# RADC-RS485-S04-V00.net
KiCad netlist of a schematic drawn in Altium Designer
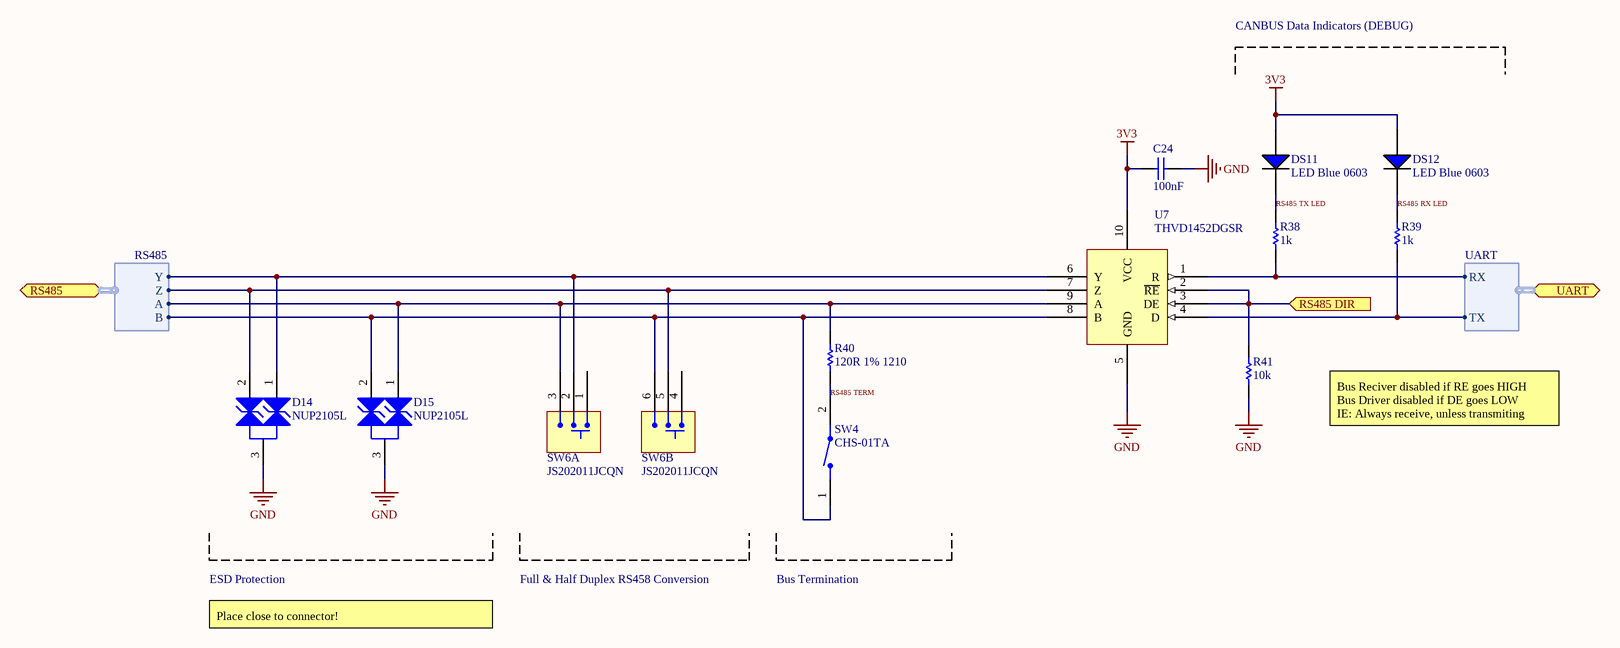
[diagram p0: RADC-RS485-S04-V00.SchDoc]

(export (version "E")
  (design (tool "Eeschema 10.0.6"))
  (components
    (comp (ref "C24")
      (value "100nF")
      (footprint "Cap_Ceramic_0603")
      (description "Capacitor, Ceramic, SMD, 100nF, 50V, 5%, X7R, 0603")
      (libsource (lib "StandardCapacitors") (part "100nF 50V 5% X7R 0603"))
    )
    (comp (ref "D14")
      (value "NUP2105L")
      (footprint "NUP2105L")
      (libsource (lib "QUTMS_CANLibrary") (part "NUP2105L"))
    )
    (comp (ref "D15")
      (value "NUP2105L")
      (footprint "NUP2105L")
      (libsource (lib "QUTMS_CANLibrary") (part "NUP2105L"))
    )
    (comp (ref "DS11")
      (value "LED Blue 0603")
      (footprint "LED BLUE 0603")
      (libsource (lib "QUTMS_LEDLibrary") (part "LED BLUE 0603"))
    )
    (comp (ref "DS12")
      (value "LED Blue 0603")
      (footprint "LED BLUE 0603")
      (libsource (lib "QUTMS_LEDLibrary") (part "LED BLUE 0603"))
    )
    (comp (ref "R38")
      (value "1k")
      (footprint "Res_ThinFilm_0603")
      (description "Resistor, SMD, 1k, 0.1W, 5%, 0603")
      (libsource (lib "StandardResistors") (part "1k 5% 0603"))
    )
    (comp (ref "R39")
      (value "1k")
      (footprint "Res_ThinFilm_0603")
      (description "Resistor, SMD, 1k, 0.1W, 5%, 0603")
      (libsource (lib "StandardResistors") (part "1k 5% 0603"))
    )
    (comp (ref "R40")
      (value "120R 1% 1210")
      (footprint "Res_ThinFilm_1210")
      (description "Resistor, SMD, 120R, 0.25W, 1%, 1210")
      (libsource (lib "StandardResistors") (part "120R 1% 1210"))
    )
    (comp (ref "R41")
      (value "10k")
      (footprint "Res_ThinFilm_0603")
      (description "Resistor, SMD, 10k, 0.1W, 5%, 0603")
      (libsource (lib "StandardResistors") (part "10k 5% 0603"))
    )
    (comp (ref "SW4")
      (value "CHS-01TA")
      (footprint "CHS-01TA")
      (description "Dip Switch SPST 1 Position Surface Mount Slide (Standard) Actuator 100mA 6VDC")
      (libsource (lib "QUTMS_SwitchLibrary") (part "CHS-01TA"))
    )
    (comp (ref "SW6")
      (value "JS202011JCQN")
      (footprint "JS202011JCQN")
      (libsource (lib "QUTMS_SwitchLibrary") (part "SLIDE DPDT JS202011JCQN"))
    )
    (comp (ref "U7")
      (value "THVD1452DGSR")
      (footprint "10-VSSOP")
      (description "1/1 Transceiver Full RS485 10-VSSOP")
      (libsource (lib "QUTMS_IntegratedCircuitLibrary") (part "THVD1452DGSR"))
    )
  )
  (nets
    (net (code "3") (name "/RS485 DIR") (class "Default")
      (node (ref "R41") (pin "2") (pinfunction "2_2") (pintype "passive"))
      (node (ref "U7") (pin "2") (pinfunction "~{RE}_2") (pintype "input"))
      (node (ref "U7") (pin "3") (pinfunction "DE_3") (pintype "input"))
    )
    (net (code "4") (name "/RS485 RX LED") (class "Default")
      (node (ref "DS12") (pin "2") (pinfunction "C_2") (pintype "passive"))
      (node (ref "R39") (pin "2") (pinfunction "2_2") (pintype "passive"))
    )
    (net (code "5") (name "/RS485 TERM") (class "Default")
      (node (ref "R40") (pin "1") (pinfunction "1_1") (pintype "passive"))
      (node (ref "SW4") (pin "2") (pinfunction "2_2") (pintype "passive"))
    )
    (net (code "6") (name "/RS485 TX LED") (class "Default")
      (node (ref "DS11") (pin "2") (pinfunction "C_2") (pintype "passive"))
      (node (ref "R38") (pin "2") (pinfunction "2_2") (pintype "passive"))
    )
    (net (code "9") (name "3V3") (class "Default")
      (node (ref "C24") (pin "1") (pinfunction "1_1") (pintype "passive"))
      (node (ref "DS11") (pin "1") (pinfunction "A_1") (pintype "passive"))
      (node (ref "DS12") (pin "1") (pinfunction "A_1") (pintype "passive"))
      (node (ref "U7") (pin "10") (pinfunction "VCC_10") (pintype "passive"))
    )
    (net (code "10") (name "GND") (class "Default")
      (node (ref "C24") (pin "2") (pinfunction "2_2") (pintype "passive"))
      (node (ref "D14") (pin "3") (pinfunction "3_3") (pintype "passive"))
      (node (ref "D15") (pin "3") (pinfunction "3_3") (pintype "passive"))
      (node (ref "R41") (pin "1") (pinfunction "1_1") (pintype "passive"))
      (node (ref "U7") (pin "5") (pinfunction "GND_5") (pintype "passive"))
    )
    (net (code "11") (name "Net-(U7-A)") (class "Default")
      (node (ref "D15") (pin "1") (pinfunction "1_1") (pintype "passive"))
      (node (ref "R40") (pin "2") (pinfunction "2_2") (pintype "passive"))
      (node (ref "SW6") (pin "3") (pinfunction "3_3") (pintype "passive"))
      (node (ref "U7") (pin "9") (pinfunction "A_9") (pintype "passive"))
    )
    (net (code "12") (name "Net-(U7-B)") (class "Default")
      (node (ref "D15") (pin "2") (pinfunction "2_2") (pintype "passive"))
      (node (ref "SW4") (pin "1") (pinfunction "1_1") (pintype "passive"))
      (node (ref "SW6") (pin "6") (pinfunction "6_6") (pintype "passive"))
      (node (ref "U7") (pin "8") (pinfunction "B_8") (pintype "passive"))
    )
    (net (code "13") (name "Net-(U7-D)") (class "Default")
      (node (ref "R39") (pin "1") (pinfunction "1_1") (pintype "passive"))
      (node (ref "U7") (pin "4") (pinfunction "D_4") (pintype "input"))
    )
    (net (code "14") (name "Net-(U7-R)") (class "Default")
      (node (ref "R38") (pin "1") (pinfunction "1_1") (pintype "passive"))
      (node (ref "U7") (pin "1") (pinfunction "R_1") (pintype "output"))
    )
    (net (code "15") (name "Net-(U7-Y)") (class "Default")
      (node (ref "D14") (pin "1") (pinfunction "1_1") (pintype "passive"))
      (node (ref "SW6") (pin "2") (pinfunction "2_2") (pintype "passive"))
      (node (ref "U7") (pin "6") (pinfunction "Y_6") (pintype "passive"))
    )
    (net (code "16") (name "Net-(U7-Z)") (class "Default")
      (node (ref "D14") (pin "2") (pinfunction "2_2") (pintype "passive"))
      (node (ref "SW6") (pin "5") (pinfunction "5_5") (pintype "passive"))
      (node (ref "U7") (pin "7") (pinfunction "Z_7") (pintype "passive"))
    )
    (net (code "17") (name "unconnected-(SW6-Pad1)") (class "Default")
      (node (ref "SW6") (pin "1") (pinfunction "1_1") (pintype "passive"))
    )
    (net (code "18") (name "unconnected-(SW6-Pad4)") (class "Default")
      (node (ref "SW6") (pin "4") (pinfunction "4_4") (pintype "passive"))
    )
  )
)
